# SPTSquidBoard.net
KiCad netlist of a schematic drawn in Altium Designer
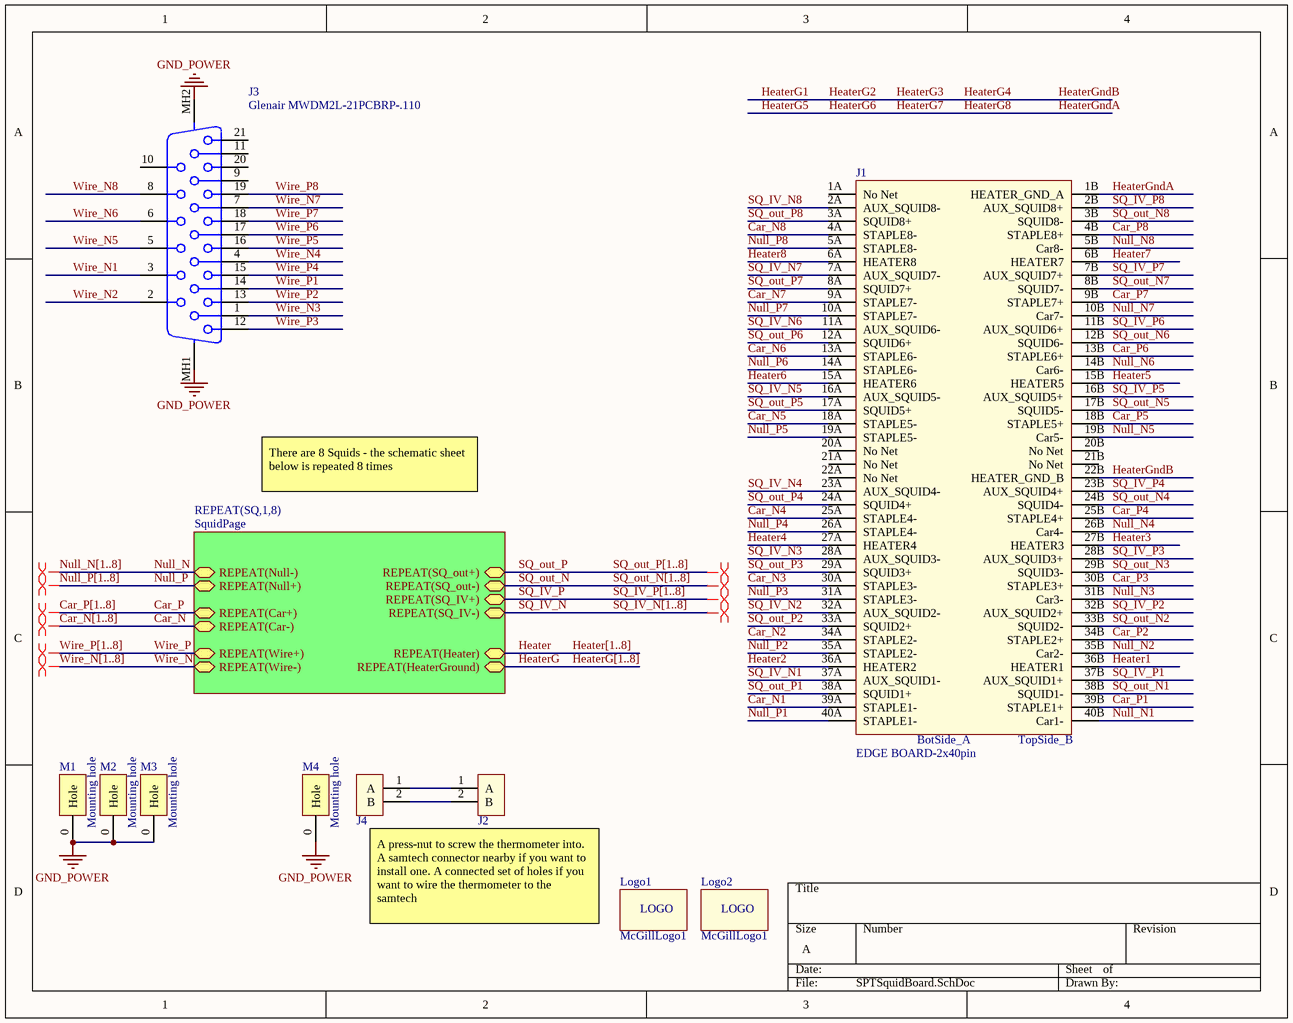
[diagram p0: SPTSquidBoard.SchDoc]

(export (version "E")
  (design (tool "Eeschema 10.0.6"))
  (components
    (comp (ref "J1")
      (value "EDGE BOARD-2x40pin")
      (description "Edge connector")
      (libsource (lib "SPT3G_LCBoard") (part "EDGE BOARD-2x40pin"))
    )
    (comp (ref "J2")
      (value "TempSenseWireConnection")
      (footprint "TempSenseWireCons")
      (libsource (lib "") (part "TempSenseCon_1"))
    )
    (comp (ref "J3")
      (value "Glenair MWDM2L-21PCBRP-.110")
      (footprint "MicroD21Glenair-Pin-RA3row")
      (description "Glenair 21pin RA Micro Dsub socket - MWDM2L-21PCBRP-.110")
      (libsource (lib "SPT3G_LCBoard") (part "MWDM2L-21PCBRP-.110"))
    )
    (comp (ref "J4")
      (value "TempSenseWireConnection")
      (footprint "TempSenseWireCons")
      (libsource (lib "SPT3G_LCBoard") (part "TempSenseCon"))
    )
    (comp (ref "Logo1")
      (value "McGillLogo1")
      (footprint "McGillLogo1")
      (libsource (lib "SPT3G_LCBoard") (part "Logo"))
    )
    (comp (ref "Logo2")
      (value "McGillLogo1")
      (footprint "McGillLogo1")
      (libsource (lib "SPT3G_LCBoard") (part "Logo"))
    )
    (comp (ref "M1")
      (value "Mounting hole")
      (footprint "MountingHoleSquidBoard")
      (libsource (lib "SPT3G_LCBoard") (part "SquidBoardMountingHole"))
    )
    (comp (ref "M2")
      (value "Mounting hole")
      (footprint "MountingHoleSquidBoard")
      (libsource (lib "SPT3G_LCBoard") (part "SquidBoardMountingHole"))
    )
    (comp (ref "M3")
      (value "Mounting hole")
      (footprint "MountingHoleSquidBoard")
      (libsource (lib "SPT3G_LCBoard") (part "SquidBoardMountingHole"))
    )
    (comp (ref "M4")
      (value "Mounting hole")
      (footprint "MountingHoleSquidBoard")
      (libsource (lib "SPT3G_LCBoard") (part "SquidBoardMountingHole"))
    )
  )
  (nets
    (net (code "2") (name "/Car_N1") (class "Default")
      (node (ref "J1") (pin "39A") (pinfunction "STAPLE1-_39A") (pintype "passive"))
    )
    (net (code "3") (name "/Car_N2") (class "Default")
      (node (ref "J1") (pin "34A") (pinfunction "STAPLE2-_34A") (pintype "passive"))
    )
    (net (code "4") (name "/Car_N3") (class "Default")
      (node (ref "J1") (pin "30A") (pinfunction "STAPLE3-_30A") (pintype "passive"))
    )
    (net (code "5") (name "/Car_N4") (class "Default")
      (node (ref "J1") (pin "25A") (pinfunction "STAPLE4-_25A") (pintype "passive"))
    )
    (net (code "6") (name "/Car_N5") (class "Default")
      (node (ref "J1") (pin "18A") (pinfunction "STAPLE5-_18A") (pintype "passive"))
    )
    (net (code "7") (name "/Car_N6") (class "Default")
      (node (ref "J1") (pin "13A") (pinfunction "STAPLE6-_13A") (pintype "passive"))
    )
    (net (code "8") (name "/Car_N7") (class "Default")
      (node (ref "J1") (pin "9A") (pinfunction "STAPLE7-_9A") (pintype "passive"))
    )
    (net (code "9") (name "/Car_N8") (class "Default")
      (node (ref "J1") (pin "4A") (pinfunction "STAPLE8-_4A") (pintype "passive"))
    )
    (net (code "12") (name "/Car_P1") (class "Default")
      (node (ref "J1") (pin "39B") (pinfunction "STAPLE1+_39B") (pintype "passive"))
    )
    (net (code "13") (name "/Car_P2") (class "Default")
      (node (ref "J1") (pin "34B") (pinfunction "STAPLE2+_34B") (pintype "passive"))
    )
    (net (code "14") (name "/Car_P3") (class "Default")
      (node (ref "J1") (pin "30B") (pinfunction "STAPLE3+_30B") (pintype "passive"))
    )
    (net (code "15") (name "/Car_P4") (class "Default")
      (node (ref "J1") (pin "25B") (pinfunction "STAPLE4+_25B") (pintype "passive"))
    )
    (net (code "16") (name "/Car_P5") (class "Default")
      (node (ref "J1") (pin "18B") (pinfunction "STAPLE5+_18B") (pintype "passive"))
    )
    (net (code "17") (name "/Car_P6") (class "Default")
      (node (ref "J1") (pin "13B") (pinfunction "STAPLE6+_13B") (pintype "passive"))
    )
    (net (code "18") (name "/Car_P7") (class "Default")
      (node (ref "J1") (pin "9B") (pinfunction "STAPLE7+_9B") (pintype "passive"))
    )
    (net (code "19") (name "/Car_P8") (class "Default")
      (node (ref "J1") (pin "4B") (pinfunction "STAPLE8+_4B") (pintype "passive"))
    )
    (net (code "22") (name "/Heater1") (class "Default")
      (node (ref "J1") (pin "36B") (pinfunction "HEATER1_36B") (pintype "passive"))
    )
    (net (code "23") (name "/Heater2") (class "Default")
      (node (ref "J1") (pin "36A") (pinfunction "HEATER2_36A") (pintype "passive"))
    )
    (net (code "24") (name "/Heater3") (class "Default")
      (node (ref "J1") (pin "27B") (pinfunction "HEATER3_27B") (pintype "passive"))
    )
    (net (code "25") (name "/Heater4") (class "Default")
      (node (ref "J1") (pin "27A") (pinfunction "HEATER4_27A") (pintype "passive"))
    )
    (net (code "26") (name "/Heater5") (class "Default")
      (node (ref "J1") (pin "15B") (pinfunction "HEATER5_15B") (pintype "passive"))
    )
    (net (code "27") (name "/Heater6") (class "Default")
      (node (ref "J1") (pin "15A") (pinfunction "HEATER6_15A") (pintype "passive"))
    )
    (net (code "28") (name "/Heater7") (class "Default")
      (node (ref "J1") (pin "6B") (pinfunction "HEATER7_6B") (pintype "passive"))
    )
    (net (code "29") (name "/Heater8") (class "Default")
      (node (ref "J1") (pin "6A") (pinfunction "HEATER8_6A") (pintype "passive"))
    )
    (net (code "31") (name "/HeaterG1") (class "Default")
      (node (ref "J1") (pin "22B") (pinfunction "HEATER_GND_B_22B") (pintype "passive"))
    )
    (net (code "32") (name "/HeaterG5") (class "Default")
      (node (ref "J1") (pin "1B") (pinfunction "HEATER_GND_A_1B") (pintype "passive"))
    )
    (net (code "34") (name "/Null_N1") (class "Default")
      (node (ref "J1") (pin "40B") (pinfunction "Car1-_40B") (pintype "passive"))
    )
    (net (code "35") (name "/Null_N2") (class "Default")
      (node (ref "J1") (pin "35B") (pinfunction "Car2-_35B") (pintype "passive"))
    )
    (net (code "36") (name "/Null_N3") (class "Default")
      (node (ref "J1") (pin "31B") (pinfunction "Car3-_31B") (pintype "passive"))
    )
    (net (code "37") (name "/Null_N4") (class "Default")
      (node (ref "J1") (pin "26B") (pinfunction "Car4-_26B") (pintype "passive"))
    )
    (net (code "38") (name "/Null_N5") (class "Default")
      (node (ref "J1") (pin "19B") (pinfunction "Car5-_19B") (pintype "passive"))
    )
    (net (code "39") (name "/Null_N6") (class "Default")
      (node (ref "J1") (pin "14B") (pinfunction "Car6-_14B") (pintype "passive"))
    )
    (net (code "40") (name "/Null_N7") (class "Default")
      (node (ref "J1") (pin "10B") (pinfunction "Car7-_10B") (pintype "passive"))
    )
    (net (code "41") (name "/Null_N8") (class "Default")
      (node (ref "J1") (pin "5B") (pinfunction "Car8-_5B") (pintype "passive"))
    )
    (net (code "44") (name "/Null_P1") (class "Default")
      (node (ref "J1") (pin "40A") (pinfunction "STAPLE1-_40A") (pintype "passive"))
    )
    (net (code "45") (name "/Null_P2") (class "Default")
      (node (ref "J1") (pin "35A") (pinfunction "STAPLE2-_35A") (pintype "passive"))
    )
    (net (code "46") (name "/Null_P3") (class "Default")
      (node (ref "J1") (pin "31A") (pinfunction "STAPLE3-_31A") (pintype "passive"))
    )
    (net (code "47") (name "/Null_P4") (class "Default")
      (node (ref "J1") (pin "26A") (pinfunction "STAPLE4-_26A") (pintype "passive"))
    )
    (net (code "48") (name "/Null_P5") (class "Default")
      (node (ref "J1") (pin "19A") (pinfunction "STAPLE5-_19A") (pintype "passive"))
    )
    (net (code "49") (name "/Null_P6") (class "Default")
      (node (ref "J1") (pin "14A") (pinfunction "STAPLE6-_14A") (pintype "passive"))
    )
    (net (code "50") (name "/Null_P7") (class "Default")
      (node (ref "J1") (pin "10A") (pinfunction "STAPLE7-_10A") (pintype "passive"))
    )
    (net (code "51") (name "/Null_P8") (class "Default")
      (node (ref "J1") (pin "5A") (pinfunction "STAPLE8-_5A") (pintype "passive"))
    )
    (net (code "54") (name "/SQ_IV_N1") (class "Default")
      (node (ref "J1") (pin "37A") (pinfunction "AUX_SQUID1-_37A") (pintype "passive"))
    )
    (net (code "55") (name "/SQ_IV_N2") (class "Default")
      (node (ref "J1") (pin "32A") (pinfunction "AUX_SQUID2-_32A") (pintype "passive"))
    )
    (net (code "56") (name "/SQ_IV_N3") (class "Default")
      (node (ref "J1") (pin "28A") (pinfunction "AUX_SQUID3-_28A") (pintype "passive"))
    )
    (net (code "57") (name "/SQ_IV_N4") (class "Default")
      (node (ref "J1") (pin "23A") (pinfunction "AUX_SQUID4-_23A") (pintype "passive"))
    )
    (net (code "58") (name "/SQ_IV_N5") (class "Default")
      (node (ref "J1") (pin "16A") (pinfunction "AUX_SQUID5-_16A") (pintype "passive"))
    )
    (net (code "59") (name "/SQ_IV_N6") (class "Default")
      (node (ref "J1") (pin "11A") (pinfunction "AUX_SQUID6-_11A") (pintype "passive"))
    )
    (net (code "60") (name "/SQ_IV_N7") (class "Default")
      (node (ref "J1") (pin "7A") (pinfunction "AUX_SQUID7-_7A") (pintype "passive"))
    )
    (net (code "61") (name "/SQ_IV_N8") (class "Default")
      (node (ref "J1") (pin "2A") (pinfunction "AUX_SQUID8-_2A") (pintype "passive"))
    )
    (net (code "64") (name "/SQ_IV_P1") (class "Default")
      (node (ref "J1") (pin "37B") (pinfunction "AUX_SQUID1+_37B") (pintype "passive"))
    )
    (net (code "65") (name "/SQ_IV_P2") (class "Default")
      (node (ref "J1") (pin "32B") (pinfunction "AUX_SQUID2+_32B") (pintype "passive"))
    )
    (net (code "66") (name "/SQ_IV_P3") (class "Default")
      (node (ref "J1") (pin "28B") (pinfunction "AUX_SQUID3+_28B") (pintype "passive"))
    )
    (net (code "67") (name "/SQ_IV_P4") (class "Default")
      (node (ref "J1") (pin "23B") (pinfunction "AUX_SQUID4+_23B") (pintype "passive"))
    )
    (net (code "68") (name "/SQ_IV_P5") (class "Default")
      (node (ref "J1") (pin "16B") (pinfunction "AUX_SQUID5+_16B") (pintype "passive"))
    )
    (net (code "69") (name "/SQ_IV_P6") (class "Default")
      (node (ref "J1") (pin "11B") (pinfunction "AUX_SQUID6+_11B") (pintype "passive"))
    )
    (net (code "70") (name "/SQ_IV_P7") (class "Default")
      (node (ref "J1") (pin "7B") (pinfunction "AUX_SQUID7+_7B") (pintype "passive"))
    )
    (net (code "71") (name "/SQ_IV_P8") (class "Default")
      (node (ref "J1") (pin "2B") (pinfunction "AUX_SQUID8+_2B") (pintype "passive"))
    )
    (net (code "74") (name "/SQ_out_N1") (class "Default")
      (node (ref "J1") (pin "38B") (pinfunction "SQUID1-_38B") (pintype "passive"))
    )
    (net (code "75") (name "/SQ_out_N2") (class "Default")
      (node (ref "J1") (pin "33B") (pinfunction "SQUID2-_33B") (pintype "passive"))
    )
    (net (code "76") (name "/SQ_out_N3") (class "Default")
      (node (ref "J1") (pin "29B") (pinfunction "SQUID3-_29B") (pintype "passive"))
    )
    (net (code "77") (name "/SQ_out_N4") (class "Default")
      (node (ref "J1") (pin "24B") (pinfunction "SQUID4-_24B") (pintype "passive"))
    )
    (net (code "78") (name "/SQ_out_N5") (class "Default")
      (node (ref "J1") (pin "17B") (pinfunction "SQUID5-_17B") (pintype "passive"))
    )
    (net (code "79") (name "/SQ_out_N6") (class "Default")
      (node (ref "J1") (pin "12B") (pinfunction "SQUID6-_12B") (pintype "passive"))
    )
    (net (code "80") (name "/SQ_out_N7") (class "Default")
      (node (ref "J1") (pin "8B") (pinfunction "SQUID7-_8B") (pintype "passive"))
    )
    (net (code "81") (name "/SQ_out_N8") (class "Default")
      (node (ref "J1") (pin "3B") (pinfunction "SQUID8-_3B") (pintype "passive"))
    )
    (net (code "84") (name "/SQ_out_P1") (class "Default")
      (node (ref "J1") (pin "38A") (pinfunction "SQUID1+_38A") (pintype "passive"))
    )
    (net (code "85") (name "/SQ_out_P2") (class "Default")
      (node (ref "J1") (pin "33A") (pinfunction "SQUID2+_33A") (pintype "passive"))
    )
    (net (code "86") (name "/SQ_out_P3") (class "Default")
      (node (ref "J1") (pin "29A") (pinfunction "SQUID3+_29A") (pintype "passive"))
    )
    (net (code "87") (name "/SQ_out_P4") (class "Default")
      (node (ref "J1") (pin "24A") (pinfunction "SQUID4+_24A") (pintype "passive"))
    )
    (net (code "88") (name "/SQ_out_P5") (class "Default")
      (node (ref "J1") (pin "17A") (pinfunction "SQUID5+_17A") (pintype "passive"))
    )
    (net (code "89") (name "/SQ_out_P6") (class "Default")
      (node (ref "J1") (pin "12A") (pinfunction "SQUID6+_12A") (pintype "passive"))
    )
    (net (code "90") (name "/SQ_out_P7") (class "Default")
      (node (ref "J1") (pin "8A") (pinfunction "SQUID7+_8A") (pintype "passive"))
    )
    (net (code "91") (name "/SQ_out_P8") (class "Default")
      (node (ref "J1") (pin "3A") (pinfunction "SQUID8+_3A") (pintype "passive"))
    )
    (net (code "94") (name "/Wire_N1") (class "Default")
      (node (ref "J3") (pin "3") (pinfunction "3_3") (pintype "passive"))
    )
    (net (code "95") (name "/Wire_N2") (class "Default")
      (node (ref "J3") (pin "2") (pinfunction "2_2") (pintype "passive"))
    )
    (net (code "96") (name "/Wire_N3") (class "Default")
      (node (ref "J3") (pin "1") (pinfunction "1_1") (pintype "passive"))
    )
    (net (code "97") (name "/Wire_N4") (class "Default")
      (node (ref "J3") (pin "4") (pinfunction "4_4") (pintype "passive"))
    )
    (net (code "98") (name "/Wire_N5") (class "Default")
      (node (ref "J3") (pin "5") (pinfunction "5_5") (pintype "passive"))
    )
    (net (code "99") (name "/Wire_N6") (class "Default")
      (node (ref "J3") (pin "6") (pinfunction "6_6") (pintype "passive"))
    )
    (net (code "100") (name "/Wire_N7") (class "Default")
      (node (ref "J3") (pin "7") (pinfunction "7_7") (pintype "passive"))
    )
    (net (code "101") (name "/Wire_N8") (class "Default")
      (node (ref "J3") (pin "8") (pinfunction "8_8") (pintype "passive"))
    )
    (net (code "104") (name "/Wire_P1") (class "Default")
      (node (ref "J3") (pin "14") (pinfunction "14_14") (pintype "passive"))
    )
    (net (code "105") (name "/Wire_P2") (class "Default")
      (node (ref "J3") (pin "13") (pinfunction "13_13") (pintype "passive"))
    )
    (net (code "106") (name "/Wire_P3") (class "Default")
      (node (ref "J3") (pin "12") (pinfunction "12_12") (pintype "passive"))
    )
    (net (code "107") (name "/Wire_P4") (class "Default")
      (node (ref "J3") (pin "15") (pinfunction "15_15") (pintype "passive"))
    )
    (net (code "108") (name "/Wire_P5") (class "Default")
      (node (ref "J3") (pin "16") (pinfunction "16_16") (pintype "passive"))
    )
    (net (code "109") (name "/Wire_P6") (class "Default")
      (node (ref "J3") (pin "17") (pinfunction "17_17") (pintype "passive"))
    )
    (net (code "110") (name "/Wire_P7") (class "Default")
      (node (ref "J3") (pin "18") (pinfunction "18_18") (pintype "passive"))
    )
    (net (code "111") (name "/Wire_P8") (class "Default")
      (node (ref "J3") (pin "19") (pinfunction "19_19") (pintype "passive"))
    )
    (net (code "113") (name "GND_POWER") (class "Default")
      (node (ref "J3") (pin "MH1") (pinfunction "MH1_MH1") (pintype "passive"))
      (node (ref "J3") (pin "MH2") (pinfunction "MH2_MH2") (pintype "passive"))
      (node (ref "M1") (pin "0") (pinfunction "Hole_0") (pintype "passive"))
      (node (ref "M2") (pin "0") (pinfunction "Hole_0") (pintype "passive"))
      (node (ref "M3") (pin "0") (pinfunction "Hole_0") (pintype "passive"))
      (node (ref "M4") (pin "0") (pinfunction "Hole_0") (pintype "passive"))
    )
    (net (code "114") (name "Net-(J2-A)") (class "Default")
      (node (ref "J2") (pin "1") (pinfunction "A_1") (pintype "passive"))
      (node (ref "J4") (pin "1") (pinfunction "A_1") (pintype "passive"))
    )
    (net (code "115") (name "Net-(J2-B)") (class "Default")
      (node (ref "J2") (pin "2") (pinfunction "B_2") (pintype "passive"))
      (node (ref "J4") (pin "2") (pinfunction "B_2") (pintype "passive"))
    )
    (net (code "116") (name "unconnected-(J1-No_Net-Pad1A)") (class "Default")
      (node (ref "J1") (pin "1A") (pinfunction "No_Net_1A") (pintype "passive"))
    )
    (net (code "117") (name "unconnected-(J1-No_Net-Pad20A)") (class "Default")
      (node (ref "J1") (pin "20A") (pinfunction "No_Net_20A") (pintype "passive"))
    )
    (net (code "118") (name "unconnected-(J1-No_Net-Pad20B)") (class "Default")
      (node (ref "J1") (pin "20B") (pinfunction "No_Net_20B") (pintype "passive"))
    )
    (net (code "119") (name "unconnected-(J1-No_Net-Pad21A)") (class "Default")
      (node (ref "J1") (pin "21A") (pinfunction "No_Net_21A") (pintype "passive"))
    )
    (net (code "120") (name "unconnected-(J1-No_Net-Pad21B)") (class "Default")
      (node (ref "J1") (pin "21B") (pinfunction "No_Net_21B") (pintype "passive"))
    )
    (net (code "121") (name "unconnected-(J1-No_Net-Pad22A)") (class "Default")
      (node (ref "J1") (pin "22A") (pinfunction "No_Net_22A") (pintype "passive"))
    )
    (net (code "122") (name "unconnected-(J3-Pad9)") (class "Default")
      (node (ref "J3") (pin "9") (pinfunction "9_9") (pintype "passive"))
    )
    (net (code "123") (name "unconnected-(J3-Pad10)") (class "Default")
      (node (ref "J3") (pin "10") (pinfunction "10_10") (pintype "passive"))
    )
    (net (code "124") (name "unconnected-(J3-Pad11)") (class "Default")
      (node (ref "J3") (pin "11") (pinfunction "11_11") (pintype "passive"))
    )
    (net (code "125") (name "unconnected-(J3-Pad20)") (class "Default")
      (node (ref "J3") (pin "20") (pinfunction "20_20") (pintype "passive"))
    )
    (net (code "126") (name "unconnected-(J3-Pad21)") (class "Default")
      (node (ref "J3") (pin "21") (pinfunction "21_21") (pintype "passive"))
    )
  )
)
